# Sheet2.net
KiCad netlist of a schematic drawn in Altium Designer
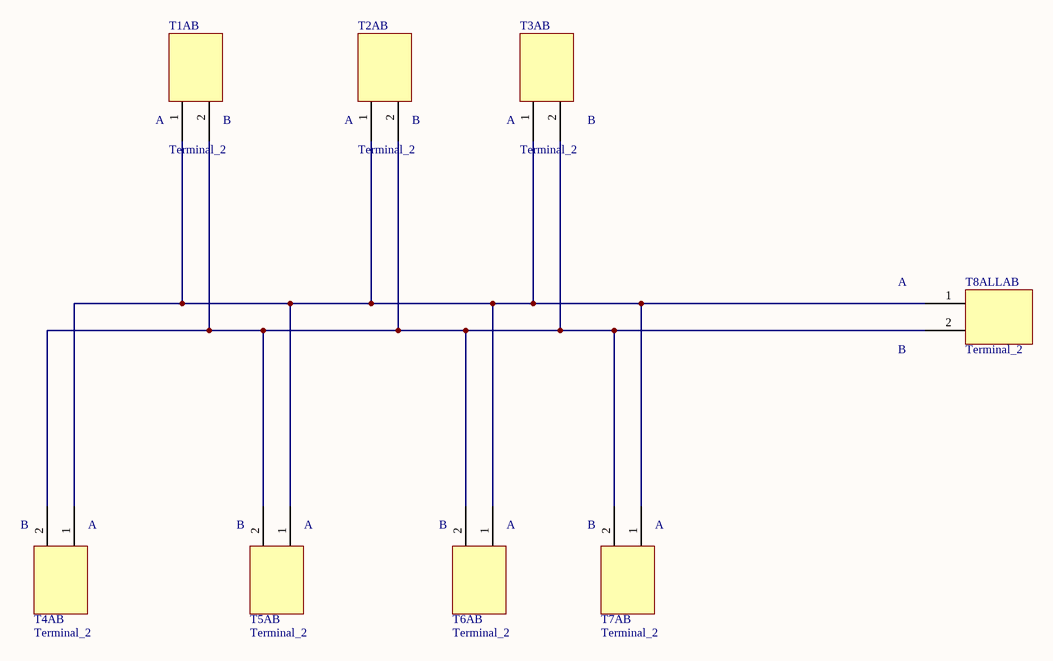
[diagram p0: Sheet2.SchDoc]

(export (version "E")
  (design (tool "Eeschema 10.0.6"))
  (components
    (comp (ref "T1AB")
      (value "Terminal_2")
      (footprint "TERMINAL_2_3.5")
      (libsource (lib "") (part "Terminal_2_1"))
    )
    (comp (ref "T2AB")
      (value "Terminal_2")
      (footprint "TERMINAL_2_3.5")
      (libsource (lib "") (part "Terminal_2_1"))
    )
    (comp (ref "T3AB")
      (value "Terminal_2")
      (footprint "TERMINAL_2_3.5")
      (libsource (lib "") (part "Terminal_2_1"))
    )
    (comp (ref "T4AB")
      (value "Terminal_2")
      (footprint "TERMINAL_2_3.5")
      (libsource (lib "my_2") (part "Terminal_2"))
    )
    (comp (ref "T5AB")
      (value "Terminal_2")
      (footprint "TERMINAL_2_3.5")
      (libsource (lib "my_2") (part "Terminal_2"))
    )
    (comp (ref "T6AB")
      (value "Terminal_2")
      (footprint "TERMINAL_2_3.5")
      (libsource (lib "my_2") (part "Terminal_2"))
    )
    (comp (ref "T7AB")
      (value "Terminal_2")
      (footprint "TERMINAL_2_3.5")
      (libsource (lib "my_2") (part "Terminal_2"))
    )
    (comp (ref "T8ALLAB")
      (value "Terminal_2")
      (footprint "TERMINAL_2_3.5")
      (libsource (lib "") (part "Terminal_2_2"))
    )
  )
  (nets
    (net (code "1") (name "Net-(T1AB-Pad1)") (class "Default")
      (node (ref "T1AB") (pin "1") (pinfunction "1_1") (pintype "passive"))
      (node (ref "T2AB") (pin "1") (pinfunction "1_1") (pintype "passive"))
      (node (ref "T3AB") (pin "1") (pinfunction "1_1") (pintype "passive"))
      (node (ref "T4AB") (pin "1") (pinfunction "1_1") (pintype "passive"))
      (node (ref "T5AB") (pin "1") (pinfunction "1_1") (pintype "passive"))
      (node (ref "T6AB") (pin "1") (pinfunction "1_1") (pintype "passive"))
      (node (ref "T7AB") (pin "1") (pinfunction "1_1") (pintype "passive"))
      (node (ref "T8ALLAB") (pin "1") (pinfunction "1_1") (pintype "passive"))
    )
    (net (code "2") (name "Net-(T1AB-Pad2)") (class "Default")
      (node (ref "T1AB") (pin "2") (pinfunction "2_2") (pintype "passive"))
      (node (ref "T2AB") (pin "2") (pinfunction "2_2") (pintype "passive"))
      (node (ref "T3AB") (pin "2") (pinfunction "2_2") (pintype "passive"))
      (node (ref "T4AB") (pin "2") (pinfunction "2_2") (pintype "passive"))
      (node (ref "T5AB") (pin "2") (pinfunction "2_2") (pintype "passive"))
      (node (ref "T6AB") (pin "2") (pinfunction "2_2") (pintype "passive"))
      (node (ref "T7AB") (pin "2") (pinfunction "2_2") (pintype "passive"))
      (node (ref "T8ALLAB") (pin "2") (pinfunction "2_2") (pintype "passive"))
    )
  )
)
